# MP2359_3_3V.net
KiCad netlist of a schematic drawn in Altium Designer
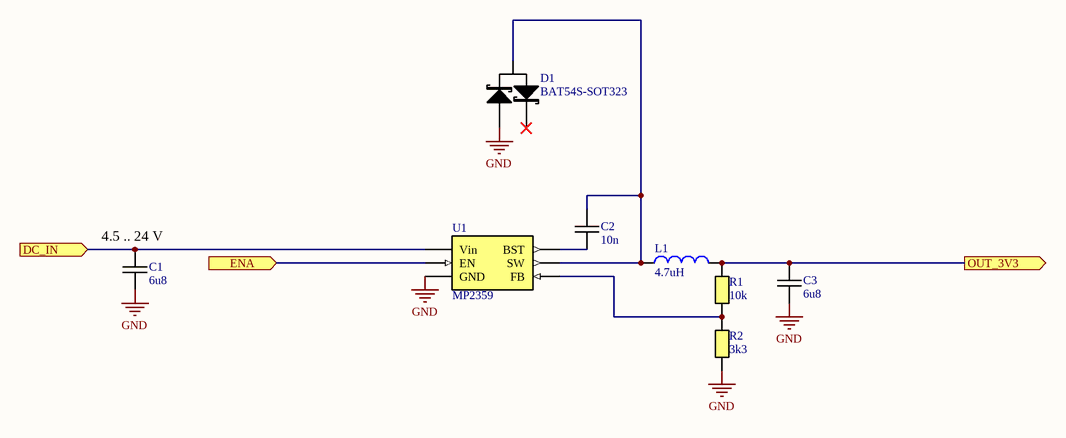
[diagram p0: MP2359_3.3V.SchDoc]

(export (version "E")
  (design (tool "Eeschema 10.0.6"))
  (components
    (comp (ref "C1")
      (value "6u8")
      (footprint "CAPC0805(2012)75_N")
      (description "Ceramic capacitor Medium density")
      (libsource (lib "Discrete_Passive_RCL") (part "Capacitor M"))
    )
    (comp (ref "C2")
      (value "10n")
      (footprint "CAPC0603(1608)55_N")
      (description "Ceramic capacitor Medium density")
      (libsource (lib "Discrete_Passive_RCL") (part "Capacitor M"))
    )
    (comp (ref "C3")
      (value "6u8")
      (footprint "CAPC0805(2012)75_N")
      (description "Ceramic capacitor Medium density")
      (libsource (lib "Discrete_Passive_RCL") (part "Capacitor M"))
    )
    (comp (ref "D1")
      (value "BAT54S-SOT323")
      (footprint "SOT323-123")
      (description "DUAL SCHOTTKY DIODE SERIES")
      (fields
        (field (name "MANUFACTURER") "NXP Semiconductors")
        (field (name "MANUFACTURER PART NUMBER") "BAT54SW,115")
      )
      (libsource (lib "vh_altium_library") (part "BAT54S-SOT323"))
    )
    (comp (ref "L1")
      (value "IND")
      (footprint "C_1210")
      (fields (field (name "INDUCTANCE") "4.7uH"))
      (libsource (lib "MyLibAltium_v1") (part "Inductor"))
    )
    (comp (ref "R1")
      (value "10k")
      (footprint "RESC0805(2012)_N")
      (description "Resistor Medium Density")
      (libsource (lib "Discrete_Passive_RCL") (part "Resistor M"))
    )
    (comp (ref "R2")
      (value "3k3")
      (footprint "RESC0805(2012)_N")
      (description "Resistor Medium Density")
      (libsource (lib "Discrete_Passive_RCL") (part "Resistor M"))
    )
    (comp (ref "U1")
      (value "MP2359")
      (footprint "TSOP23-6")
      (description "monolithic step-down switch  mode converter with a built-in power MOSFET")
      (libsource (lib "MyLibAltium_v1") (part "MP2359"))
    )
  )
  (nets
    (net (code "1") (name "/DC_IN") (class "Default")
      (node (ref "C1") (pin "1") (pinfunction "1_1") (pintype "passive"))
      (node (ref "U1") (pin "5") (pinfunction "Vin_5") (pintype "power_in"))
    )
    (net (code "2") (name "/ENA") (class "Default")
      (node (ref "U1") (pin "4") (pinfunction "EN_4") (pintype "input"))
    )
    (net (code "3") (name "/OUT_3V3") (class "Default")
      (node (ref "C3") (pin "1") (pinfunction "1_1") (pintype "passive"))
      (node (ref "L1") (pin "2") (pinfunction "2_2") (pintype "passive"))
      (node (ref "R1") (pin "2") (pinfunction "2_2") (pintype "passive"))
    )
    (net (code "4") (name "GND") (class "Default")
      (node (ref "C1") (pin "2") (pinfunction "2_2") (pintype "passive"))
      (node (ref "C3") (pin "2") (pinfunction "2_2") (pintype "passive"))
      (node (ref "D1") (pin "1") (pinfunction "1_1") (pintype "passive"))
      (node (ref "R2") (pin "1") (pinfunction "1_1") (pintype "passive"))
      (node (ref "U1") (pin "2") (pinfunction "GND_2") (pintype "power_in"))
    )
    (net (code "5") (name "Net-(U1-BST)") (class "Default")
      (node (ref "C2") (pin "1") (pinfunction "1_1") (pintype "passive"))
      (node (ref "U1") (pin "1") (pinfunction "BST_1") (pintype "output"))
    )
    (net (code "6") (name "Net-(U1-FB)") (class "Default")
      (node (ref "R1") (pin "1") (pinfunction "1_1") (pintype "passive"))
      (node (ref "R2") (pin "2") (pinfunction "2_2") (pintype "passive"))
      (node (ref "U1") (pin "3") (pinfunction "FB_3") (pintype "input"))
    )
    (net (code "7") (name "Net-(U1-SW)") (class "Default")
      (node (ref "C2") (pin "2") (pinfunction "2_2") (pintype "passive"))
      (node (ref "D1") (pin "3") (pinfunction "3_3") (pintype "passive"))
      (node (ref "L1") (pin "1") (pinfunction "1_1") (pintype "passive"))
      (node (ref "U1") (pin "6") (pinfunction "SW_6") (pintype "output"))
    )
    (net (code "8") (name "unconnected-(D1-Pad2)") (class "Default")
      (node (ref "D1") (pin "2") (pinfunction "2_2") (pintype "passive+no_connect"))
    )
  )
)
